# hm2.net
KiCad netlist of a schematic drawn in EAGLE
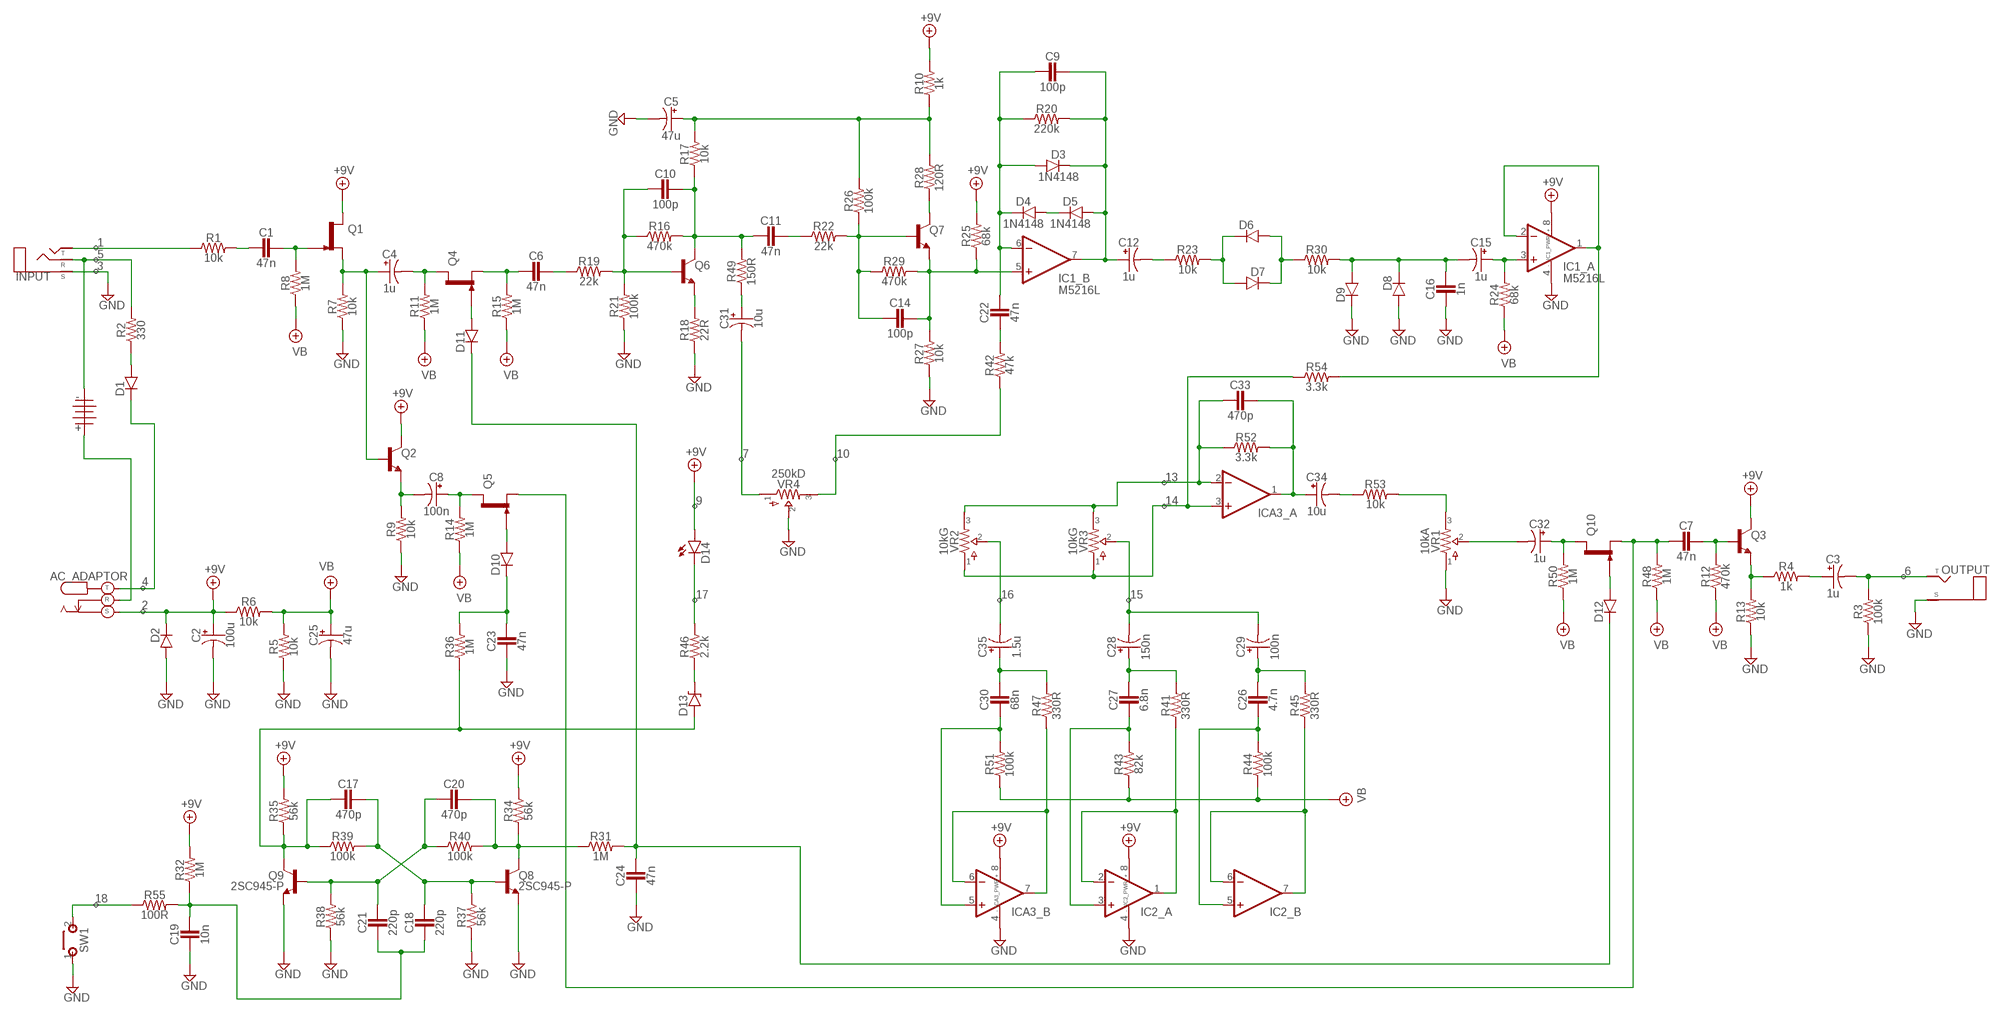
[diagram p0: schematic, sheet 1]

(export (version "E")
  (design (tool "Eeschema 10.0.6"))
  (components
    (comp (ref "1101")
      (value "BATTERY")
      (footprint "eagle-import:TWO_PADS")
      (libsource (lib "eagle-import") (part "BATTERY"))
    )
    (comp (ref "AC_ADAPTOR")
      (value "DC_KOBICONN")
      (footprint "eagle-import:DC_KOBICONN")
      (libsource (lib "eagle-import") (part "DC_KOBICONN"))
    )
    (comp (ref "C1")
      (value "47n")
      (footprint "eagle-import:BOX_SMALL")
      (libsource (lib "eagle-import") (part "CER/FILMBOX.1"))
    )
    (comp (ref "C2")
      (value "100u")
      (footprint "eagle-import:040_020")
      (libsource (lib "eagle-import") (part "0400"))
    )
    (comp (ref "C3")
      (value "1u")
      (footprint "eagle-import:040_020")
      (libsource (lib "eagle-import") (part "0400"))
    )
    (comp (ref "C4")
      (value "1u")
      (footprint "eagle-import:040_020")
      (libsource (lib "eagle-import") (part "0400"))
    )
    (comp (ref "C5")
      (value "47u")
      (footprint "eagle-import:040_020")
      (libsource (lib "eagle-import") (part "0400"))
    )
    (comp (ref "C6")
      (value "47n")
      (footprint "eagle-import:BOX_SMALL")
      (libsource (lib "eagle-import") (part "CER/FILMBOX.1"))
    )
    (comp (ref "C7")
      (value "47n")
      (footprint "eagle-import:BOX_SMALL")
      (libsource (lib "eagle-import") (part "CER/FILMBOX.1"))
    )
    (comp (ref "C8")
      (value "100n")
      (footprint "eagle-import:040_020")
      (libsource (lib "eagle-import") (part "0400"))
    )
    (comp (ref "C9")
      (value "100p")
      (footprint "eagle-import:BOX_SMALL")
      (libsource (lib "eagle-import") (part "CER/FILMBOX.1"))
    )
    (comp (ref "C10")
      (value "100p")
      (footprint "eagle-import:BOX_SMALL")
      (libsource (lib "eagle-import") (part "CER/FILMBOX.1"))
    )
    (comp (ref "C11")
      (value "47n")
      (footprint "eagle-import:BOX_SMALL")
      (libsource (lib "eagle-import") (part "CER/FILMBOX.1"))
    )
    (comp (ref "C12")
      (value "1u")
      (footprint "eagle-import:040_020")
      (libsource (lib "eagle-import") (part "0400"))
    )
    (comp (ref "C14")
      (value "100p")
      (footprint "eagle-import:BOX_SMALL")
      (libsource (lib "eagle-import") (part "CER/FILMBOX.1"))
    )
    (comp (ref "C15")
      (value "1u")
      (footprint "eagle-import:040_020")
      (libsource (lib "eagle-import") (part "0400"))
    )
    (comp (ref "C16")
      (value "1n")
      (footprint "eagle-import:BOX_SMALL")
      (libsource (lib "eagle-import") (part "CER/FILMBOX.1"))
    )
    (comp (ref "C17")
      (value "470p")
      (footprint "eagle-import:BOX_SMALL")
      (libsource (lib "eagle-import") (part "CER/FILMBOX.1"))
    )
    (comp (ref "C18")
      (value "220p")
      (footprint "eagle-import:BOX_SMALL")
      (libsource (lib "eagle-import") (part "CER/FILMBOX.1"))
    )
    (comp (ref "C19")
      (value "10n")
      (footprint "eagle-import:BOX_SMALL")
      (libsource (lib "eagle-import") (part "CER/FILMBOX.1"))
    )
    (comp (ref "C20")
      (value "470p")
      (footprint "eagle-import:BOX_SMALL")
      (libsource (lib "eagle-import") (part "CER/FILMBOX.1"))
    )
    (comp (ref "C21")
      (value "220p")
      (footprint "eagle-import:BOX_SMALL")
      (libsource (lib "eagle-import") (part "CER/FILMBOX.1"))
    )
    (comp (ref "C22")
      (value "47n")
      (footprint "eagle-import:BOX_SMALL")
      (libsource (lib "eagle-import") (part "CER/FILMBOX.1"))
    )
    (comp (ref "C23")
      (value "47n")
      (footprint "eagle-import:BOX_SMALL")
      (libsource (lib "eagle-import") (part "CER/FILMBOX.1"))
    )
    (comp (ref "C24")
      (value "47n")
      (footprint "eagle-import:BOX_SMALL")
      (libsource (lib "eagle-import") (part "CER/FILMBOX.1"))
    )
    (comp (ref "C25")
      (value "47u")
      (footprint "eagle-import:040_020")
      (libsource (lib "eagle-import") (part "0400"))
    )
    (comp (ref "C26")
      (value "4.7n")
      (footprint "eagle-import:BOX_SMALL")
      (libsource (lib "eagle-import") (part "CER/FILMBOX.1"))
    )
    (comp (ref "C27")
      (value "6.8n")
      (footprint "eagle-import:BOX_SMALL")
      (libsource (lib "eagle-import") (part "CER/FILMBOX.1"))
    )
    (comp (ref "C28")
      (value "150n")
      (footprint "eagle-import:040_020")
      (libsource (lib "eagle-import") (part "0400"))
    )
    (comp (ref "C29")
      (value "100n")
      (footprint "eagle-import:040_020")
      (libsource (lib "eagle-import") (part "0400"))
    )
    (comp (ref "C30")
      (value "68n")
      (footprint "eagle-import:BOX_SMALL")
      (libsource (lib "eagle-import") (part "CER/FILMBOX.1"))
    )
    (comp (ref "C31")
      (value "10u")
      (footprint "eagle-import:040_020")
      (libsource (lib "eagle-import") (part "0400"))
    )
    (comp (ref "C32")
      (value "1u")
      (footprint "eagle-import:040_020")
      (libsource (lib "eagle-import") (part "0400"))
    )
    (comp (ref "C33")
      (value "470p")
      (footprint "eagle-import:BOX_SMALL")
      (libsource (lib "eagle-import") (part "CER/FILMBOX.1"))
    )
    (comp (ref "C34")
      (value "10u")
      (footprint "eagle-import:040_020")
      (libsource (lib "eagle-import") (part "0400"))
    )
    (comp (ref "C35")
      (value "1.5u")
      (footprint "eagle-import:040_020")
      (libsource (lib "eagle-import") (part "0400"))
    )
    (comp (ref "D1")
      (value "DO35.2")
      (footprint "eagle-import:DO35-2")
      (libsource (lib "eagle-import") (part "DO35.2"))
    )
    (comp (ref "D2")
      (value "DO35.2")
      (footprint "eagle-import:DO35-2")
      (libsource (lib "eagle-import") (part "DO35.2"))
    )
    (comp (ref "D3")
      (value "1N4148")
      (footprint "eagle-import:DO35-2")
      (libsource (lib "eagle-import") (part "DO35.2"))
    )
    (comp (ref "D4")
      (value "1N4148")
      (footprint "eagle-import:DO35-2")
      (libsource (lib "eagle-import") (part "DO35.2"))
    )
    (comp (ref "D5")
      (value "1N4148")
      (footprint "eagle-import:DO35-2")
      (libsource (lib "eagle-import") (part "DO35.2"))
    )
    (comp (ref "D6")
      (value "DO35.2")
      (footprint "eagle-import:DO35-2")
      (libsource (lib "eagle-import") (part "DO35.2"))
    )
    (comp (ref "D7")
      (value "DO35.2")
      (footprint "eagle-import:DO35-2")
      (libsource (lib "eagle-import") (part "DO35.2"))
    )
    (comp (ref "D8")
      (value "DO35.2")
      (footprint "eagle-import:DO35-2")
      (libsource (lib "eagle-import") (part "DO35.2"))
    )
    (comp (ref "D9")
      (value "DO35.2")
      (footprint "eagle-import:DO35-2")
      (libsource (lib "eagle-import") (part "DO35.2"))
    )
    (comp (ref "D10")
      (value "DO35.2")
      (footprint "eagle-import:DO35-2")
      (libsource (lib "eagle-import") (part "DO35.2"))
    )
    (comp (ref "D11")
      (value "DO35.2")
      (footprint "eagle-import:DO35-2")
      (libsource (lib "eagle-import") (part "DO35.2"))
    )
    (comp (ref "D12")
      (value "DO35.2")
      (footprint "eagle-import:DO35-2")
      (libsource (lib "eagle-import") (part "DO35.2"))
    )
    (comp (ref "D13")
      (value "ZENER.2")
      (footprint "eagle-import:DO41-2")
      (libsource (lib "eagle-import") (part "ZENER.2"))
    )
    (comp (ref "D14")
      (value "LED")
      (footprint "eagle-import:3MM_D")
      (libsource (lib "eagle-import") (part "LED"))
    )
    (comp (ref "IC1")
      (value "M5216L")
      (footprint "eagle-import:DIL0")
      (libsource (lib "eagle-import") (part "DUALTH"))
    )
    (comp (ref "IC2")
      (value "DUALTH")
      (footprint "eagle-import:DIL0")
      (libsource (lib "eagle-import") (part "DUALTH"))
    )
    (comp (ref "ICA3")
      (value "DUALTH")
      (footprint "eagle-import:DIL0")
      (libsource (lib "eagle-import") (part "DUALTH"))
    )
    (comp (ref "INPUT")
      (value "STEREO3PADS")
      (footprint "eagle-import:THREEPADS")
      (libsource (lib "eagle-import") (part "STEREO3PADS"))
    )
    (comp (ref "OUTPUT")
      (value "MONO")
      (footprint "eagle-import:TWO_PADS")
      (libsource (lib "eagle-import") (part "MONO"))
    )
    (comp (ref "Q1")
      (value "2N5457")
      (footprint "eagle-import:TO92-")
      (libsource (lib "eagle-import") (part "2N5457"))
    )
    (comp (ref "Q2")
      (value "2SC828A")
      (footprint "eagle-import:TO92-")
      (libsource (lib "eagle-import") (part "2SC828A"))
    )
    (comp (ref "Q3")
      (value "2SC828A")
      (footprint "eagle-import:TO92-")
      (libsource (lib "eagle-import") (part "2SC828A"))
    )
    (comp (ref "Q4")
      (value "2N5457")
      (footprint "eagle-import:TO92-")
      (libsource (lib "eagle-import") (part "2N5457"))
    )
    (comp (ref "Q5")
      (value "2N5457")
      (footprint "eagle-import:TO92-")
      (libsource (lib "eagle-import") (part "2N5457"))
    )
    (comp (ref "Q6")
      (value "2SC828A")
      (footprint "eagle-import:TO92-")
      (libsource (lib "eagle-import") (part "2SC828A"))
    )
    (comp (ref "Q7")
      (value "2SC828A")
      (footprint "eagle-import:TO92-")
      (libsource (lib "eagle-import") (part "2SC828A"))
    )
    (comp (ref "Q8")
      (value "2SC945-P")
      (footprint "eagle-import:TO92-")
      (libsource (lib "eagle-import") (part "2SC828A"))
    )
    (comp (ref "Q9")
      (value "2SC945-P")
      (footprint "eagle-import:TO92-")
      (libsource (lib "eagle-import") (part "2SC828A"))
    )
    (comp (ref "Q10")
      (value "2N5457")
      (footprint "eagle-import:TO92-")
      (libsource (lib "eagle-import") (part "2N5457"))
    )
    (comp (ref "R1")
      (value "10k")
      (footprint "eagle-import:R0207_3")
      (libsource (lib "eagle-import") (part "R_.3B"))
    )
    (comp (ref "R2")
      (value "330")
      (footprint "eagle-import:R0207_3")
      (libsource (lib "eagle-import") (part "R_.3B"))
    )
    (comp (ref "R3")
      (value "100k")
      (footprint "eagle-import:R0207_3")
      (libsource (lib "eagle-import") (part "R_.3B"))
    )
    (comp (ref "R4")
      (value "1k")
      (footprint "eagle-import:R0207_3")
      (libsource (lib "eagle-import") (part "R_.3B"))
    )
    (comp (ref "R5")
      (value "10k")
      (footprint "eagle-import:R0207_3")
      (libsource (lib "eagle-import") (part "R_.3B"))
    )
    (comp (ref "R6")
      (value "10k")
      (footprint "eagle-import:R0207_3")
      (libsource (lib "eagle-import") (part "R_.3B"))
    )
    (comp (ref "R7")
      (value "10k")
      (footprint "eagle-import:R0207_3")
      (libsource (lib "eagle-import") (part "R_.3B"))
    )
    (comp (ref "R8")
      (value "1M")
      (footprint "eagle-import:R0207_3")
      (libsource (lib "eagle-import") (part "R_.3B"))
    )
    (comp (ref "R9")
      (value "10k")
      (footprint "eagle-import:R0207_3")
      (libsource (lib "eagle-import") (part "R_.3B"))
    )
    (comp (ref "R10")
      (value "1k")
      (footprint "eagle-import:R0207_3")
      (libsource (lib "eagle-import") (part "R_.3B"))
    )
    (comp (ref "R11")
      (value "1M")
      (footprint "eagle-import:R0207_3")
      (libsource (lib "eagle-import") (part "R_.3B"))
    )
    (comp (ref "R12")
      (value "470k")
      (footprint "eagle-import:R0207_3")
      (libsource (lib "eagle-import") (part "R_.3B"))
    )
    (comp (ref "R13")
      (value "10k")
      (footprint "eagle-import:R0207_3")
      (libsource (lib "eagle-import") (part "R_.3B"))
    )
    (comp (ref "R14")
      (value "1M")
      (footprint "eagle-import:R0207_3")
      (libsource (lib "eagle-import") (part "R_.3B"))
    )
    (comp (ref "R15")
      (value "1M")
      (footprint "eagle-import:R0207_3")
      (libsource (lib "eagle-import") (part "R_.3B"))
    )
    (comp (ref "R16")
      (value "470k")
      (footprint "eagle-import:R0207_3")
      (libsource (lib "eagle-import") (part "R_.3B"))
    )
    (comp (ref "R17")
      (value "10k")
      (footprint "eagle-import:R0207_3")
      (libsource (lib "eagle-import") (part "R_.3B"))
    )
    (comp (ref "R18")
      (value "22R")
      (footprint "eagle-import:R0207_3")
      (libsource (lib "eagle-import") (part "R_.3B"))
    )
    (comp (ref "R19")
      (value "22k")
      (footprint "eagle-import:R0207_3")
      (libsource (lib "eagle-import") (part "R_.3B"))
    )
    (comp (ref "R20")
      (value "220k")
      (footprint "eagle-import:R0207_3")
      (libsource (lib "eagle-import") (part "R_.3B"))
    )
    (comp (ref "R21")
      (value "100k")
      (footprint "eagle-import:R0207_3")
      (libsource (lib "eagle-import") (part "R_.3B"))
    )
    (comp (ref "R22")
      (value "22k")
      (footprint "eagle-import:R0207_3")
      (libsource (lib "eagle-import") (part "R_.3B"))
    )
    (comp (ref "R23")
      (value "10k")
      (footprint "eagle-import:R0207_3")
      (libsource (lib "eagle-import") (part "R_.3B"))
    )
    (comp (ref "R24")
      (value "68k")
      (footprint "eagle-import:R0207_3")
      (libsource (lib "eagle-import") (part "R_.3B"))
    )
    (comp (ref "R25")
      (value "68k")
      (footprint "eagle-import:R0207_3")
      (libsource (lib "eagle-import") (part "R_.3B"))
    )
    (comp (ref "R26")
      (value "100k")
      (footprint "eagle-import:R0207_3")
      (libsource (lib "eagle-import") (part "R_.3B"))
    )
    (comp (ref "R27")
      (value "10k")
      (footprint "eagle-import:R0207_3")
      (libsource (lib "eagle-import") (part "R_.3B"))
    )
    (comp (ref "R28")
      (value "120R")
      (footprint "eagle-import:R0207_3")
      (libsource (lib "eagle-import") (part "R_.3B"))
    )
    (comp (ref "R29")
      (value "470k")
      (footprint "eagle-import:R0207_3")
      (libsource (lib "eagle-import") (part "R_.3B"))
    )
    (comp (ref "R30")
      (value "10k")
      (footprint "eagle-import:R0207_3")
      (libsource (lib "eagle-import") (part "R_.3B"))
    )
    (comp (ref "R31")
      (value "1M")
      (footprint "eagle-import:R0207_3")
      (libsource (lib "eagle-import") (part "R_.3B"))
    )
    (comp (ref "R32")
      (value "1M")
      (footprint "eagle-import:R0207_3")
      (libsource (lib "eagle-import") (part "R_.3B"))
    )
    (comp (ref "R34")
      (value "56k")
      (footprint "eagle-import:R0207_3")
      (libsource (lib "eagle-import") (part "R_.3B"))
    )
    (comp (ref "R35")
      (value "56k")
      (footprint "eagle-import:R0207_3")
      (libsource (lib "eagle-import") (part "R_.3B"))
    )
    (comp (ref "R36")
      (value "1M")
      (footprint "eagle-import:R0207_3")
      (libsource (lib "eagle-import") (part "R_.3B"))
    )
    (comp (ref "R37")
      (value "56k")
      (footprint "eagle-import:R0207_3")
      (libsource (lib "eagle-import") (part "R_.3B"))
    )
    (comp (ref "R38")
      (value "56k")
      (footprint "eagle-import:R0207_3")
      (libsource (lib "eagle-import") (part "R_.3B"))
    )
    (comp (ref "R39")
      (value "100k")
      (footprint "eagle-import:R0207_3")
      (libsource (lib "eagle-import") (part "R_.3B"))
    )
    (comp (ref "R40")
      (value "100k")
      (footprint "eagle-import:R0207_3")
      (libsource (lib "eagle-import") (part "R_.3B"))
    )
    (comp (ref "R41")
      (value "330R")
      (footprint "eagle-import:R0207_3")
      (libsource (lib "eagle-import") (part "R_.3B"))
    )
    (comp (ref "R42")
      (value "47k")
      (footprint "eagle-import:R0207_3")
      (libsource (lib "eagle-import") (part "R_.3B"))
    )
    (comp (ref "R43")
      (value "82k")
      (footprint "eagle-import:R0207_3")
      (libsource (lib "eagle-import") (part "R_.3B"))
    )
    (comp (ref "R44")
      (value "100k")
      (footprint "eagle-import:R0207_3")
      (libsource (lib "eagle-import") (part "R_.3B"))
    )
    (comp (ref "R45")
      (value "330R")
      (footprint "eagle-import:R0207_3")
      (libsource (lib "eagle-import") (part "R_.3B"))
    )
    (comp (ref "R46")
      (value "2.2k")
      (footprint "eagle-import:R0207_3")
      (libsource (lib "eagle-import") (part "R_.3B"))
    )
    (comp (ref "R47")
      (value "330R")
      (footprint "eagle-import:R0207_3")
      (libsource (lib "eagle-import") (part "R_.3B"))
    )
    (comp (ref "R48")
      (value "1M")
      (footprint "eagle-import:R0207_3")
      (libsource (lib "eagle-import") (part "R_.3B"))
    )
    (comp (ref "R49")
      (value "150R")
      (footprint "eagle-import:R0207_3")
      (libsource (lib "eagle-import") (part "R_.3B"))
    )
    (comp (ref "R50")
      (value "1M")
      (footprint "eagle-import:R0207_3")
      (libsource (lib "eagle-import") (part "R_.3B"))
    )
    (comp (ref "R51")
      (value "100k")
      (footprint "eagle-import:R0207_3")
      (libsource (lib "eagle-import") (part "R_.3B"))
    )
    (comp (ref "R52")
      (value "3.3k")
      (footprint "eagle-import:R0207_3")
      (libsource (lib "eagle-import") (part "R_.3B"))
    )
    (comp (ref "R53")
      (value "10k")
      (footprint "eagle-import:R0207_3")
      (libsource (lib "eagle-import") (part "R_.3B"))
    )
    (comp (ref "R54")
      (value "3.3k")
      (footprint "eagle-import:R0207_3")
      (libsource (lib "eagle-import") (part "R_.3B"))
    )
    (comp (ref "R55")
      (value "100R")
      (footprint "eagle-import:R0207_3")
      (libsource (lib "eagle-import") (part "R_.3B"))
    )
    (comp (ref "SW1")
      (value "MOMENTARY")
      (footprint "eagle-import:SPST")
      (libsource (lib "eagle-import") (part "MOMENTARY"))
    )
    (comp (ref "VR1")
      (value "10kA")
      (footprint "eagle-import:16MM")
      (libsource (lib "eagle-import") (part "POTS16MM"))
    )
    (comp (ref "VR2")
      (value "10kG")
      (footprint "eagle-import:16MM")
      (libsource (lib "eagle-import") (part "POTS16MM"))
    )
    (comp (ref "VR3")
      (value "10kG")
      (footprint "eagle-import:16MM")
      (libsource (lib "eagle-import") (part "POTS16MM"))
    )
    (comp (ref "VR4")
      (value "250kD")
      (footprint "eagle-import:16MM")
      (libsource (lib "eagle-import") (part "POTS16MM"))
    )
  )
  (nets
    (net (code "1") (name "+9V") (class "Default")
      (node (ref "AC_ADAPTOR") (pin "S") (pinfunction "S_S") (pintype "bidirectional"))
      (node (ref "C2") (pin "+") (pinfunction "+_+") (pintype "passive"))
      (node (ref "D14") (pin "ANODE") (pinfunction "A_ANODE") (pintype "passive"))
      (node (ref "D2") (pin "C") (pinfunction "C_C") (pintype "passive"))
      (node (ref "IC1") (pin "8") (pinfunction "V+_8") (pintype "power_in"))
      (node (ref "IC2") (pin "8") (pinfunction "V+_8") (pintype "power_in"))
      (node (ref "ICA3") (pin "8") (pinfunction "V+_8") (pintype "power_in"))
      (node (ref "Q1") (pin "3") (pinfunction "D_3") (pintype "passive"))
      (node (ref "Q2") (pin "2") (pinfunction "C_2") (pintype "passive"))
      (node (ref "Q3") (pin "2") (pinfunction "C_2") (pintype "passive"))
      (node (ref "R10") (pin "2") (pinfunction "2_2") (pintype "passive"))
      (node (ref "R25") (pin "2") (pinfunction "2_2") (pintype "passive"))
      (node (ref "R32") (pin "2") (pinfunction "2_2") (pintype "passive"))
      (node (ref "R34") (pin "2") (pinfunction "2_2") (pintype "passive"))
      (node (ref "R35") (pin "2") (pinfunction "2_2") (pintype "passive"))
      (node (ref "R6") (pin "1") (pinfunction "1_1") (pintype "passive"))
    )
    (net (code "2") (name "GND") (class "Default")
      (node (ref "C16") (pin "2") (pinfunction "2_2") (pintype "passive"))
      (node (ref "C19") (pin "2") (pinfunction "2_2") (pintype "passive"))
      (node (ref "C2") (pin "-") (pinfunction "-_-") (pintype "passive"))
      (node (ref "C23") (pin "2") (pinfunction "2_2") (pintype "passive"))
      (node (ref "C24") (pin "2") (pinfunction "2_2") (pintype "passive"))
      (node (ref "C25") (pin "-") (pinfunction "-_-") (pintype "passive"))
      (node (ref "C5") (pin "-") (pinfunction "-_-") (pintype "passive"))
      (node (ref "D2") (pin "A") (pinfunction "A_A") (pintype "passive"))
      (node (ref "D8") (pin "A") (pinfunction "A_A") (pintype "passive"))
      (node (ref "D9") (pin "C") (pinfunction "C_C") (pintype "passive"))
      (node (ref "IC1") (pin "4") (pinfunction "V-_4") (pintype "power_in"))
      (node (ref "IC2") (pin "4") (pinfunction "V-_4") (pintype "power_in"))
      (node (ref "ICA3") (pin "4") (pinfunction "V-_4") (pintype "power_in"))
      (node (ref "INPUT") (pin "SLEEVE") (pinfunction "S_SLEEVE") (pintype "passive"))
      (node (ref "OUTPUT") (pin "S") (pinfunction "SLEEVE_S") (pintype "passive"))
      (node (ref "Q8") (pin "3") (pinfunction "E_3") (pintype "passive"))
      (node (ref "Q9") (pin "3") (pinfunction "E_3") (pintype "passive"))
      (node (ref "R13") (pin "1") (pinfunction "1_1") (pintype "passive"))
      (node (ref "R18") (pin "1") (pinfunction "1_1") (pintype "passive"))
      (node (ref "R21") (pin "1") (pinfunction "1_1") (pintype "passive"))
      (node (ref "R27") (pin "1") (pinfunction "1_1") (pintype "passive"))
      (node (ref "R3") (pin "1") (pinfunction "1_1") (pintype "passive"))
      (node (ref "R37") (pin "1") (pinfunction "1_1") (pintype "passive"))
      (node (ref "R38") (pin "1") (pinfunction "1_1") (pintype "passive"))
      (node (ref "R5") (pin "1") (pinfunction "1_1") (pintype "passive"))
      (node (ref "R7") (pin "1") (pinfunction "1_1") (pintype "passive"))
      (node (ref "R9") (pin "1") (pinfunction "1_1") (pintype "passive"))
      (node (ref "SW1") (pin "1") (pinfunction "P_1") (pintype "passive"))
      (node (ref "VR1") (pin "1") (pinfunction "1_1") (pintype "passive"))
      (node (ref "VR4") (pin "2") (pinfunction "2_2") (pintype "passive"))
    )
    (net (code "3") (name "Net-(1101-P$1)") (class "Default")
      (node (ref "1101") (pin "T") (pinfunction "P$1_T") (pintype "bidirectional"))
      (node (ref "AC_ADAPTOR") (pin "R") (pinfunction "R_R") (pintype "bidirectional"))
    )
    (net (code "4") (name "Net-(1101-P$2)") (class "Default")
      (node (ref "1101") (pin "S") (pinfunction "P$2_S") (pintype "bidirectional"))
      (node (ref "INPUT") (pin "RING") (pinfunction "R_RING") (pintype "passive"))
      (node (ref "R2") (pin "2") (pinfunction "2_2") (pintype "passive"))
    )
    (net (code "5") (name "Net-(AC_ADAPTOR-PadT)") (class "Default")
      (node (ref "AC_ADAPTOR") (pin "T") (pinfunction "T_T") (pintype "bidirectional"))
      (node (ref "D1") (pin "C") (pinfunction "C_C") (pintype "passive"))
    )
    (net (code "6") (name "Net-(C1-Pad2)") (class "Default")
      (node (ref "C1") (pin "2") (pinfunction "2_2") (pintype "passive"))
      (node (ref "R1") (pin "2") (pinfunction "2_2") (pintype "passive"))
    )
    (net (code "7") (name "Net-(C3-Pad+)") (class "Default")
      (node (ref "C3") (pin "+") (pinfunction "+_+") (pintype "passive"))
      (node (ref "R4") (pin "2") (pinfunction "2_2") (pintype "passive"))
    )
    (net (code "8") (name "Net-(C5-Pad+)") (class "Default")
      (node (ref "C5") (pin "+") (pinfunction "+_+") (pintype "passive"))
      (node (ref "R10") (pin "1") (pinfunction "1_1") (pintype "passive"))
      (node (ref "R17") (pin "2") (pinfunction "2_2") (pintype "passive"))
      (node (ref "R26") (pin "2") (pinfunction "2_2") (pintype "passive"))
      (node (ref "R28") (pin "2") (pinfunction "2_2") (pintype "passive"))
    )
    (net (code "9") (name "Net-(C6-Pad1)") (class "Default")
      (node (ref "C6") (pin "1") (pinfunction "1_1") (pintype "passive"))
      (node (ref "R19") (pin "1") (pinfunction "1_1") (pintype "passive"))
    )
    (net (code "10") (name "Net-(C11-Pad1)") (class "Default")
      (node (ref "C11") (pin "1") (pinfunction "1_1") (pintype "passive"))
      (node (ref "R22") (pin "1") (pinfunction "1_1") (pintype "passive"))
    )
    (net (code "11") (name "Net-(C12-Pad-)") (class "Default")
      (node (ref "C12") (pin "-") (pinfunction "-_-") (pintype "passive"))
      (node (ref "R23") (pin "1") (pinfunction "1_1") (pintype "passive"))
    )
    (net (code "12") (name "Net-(C15-Pad-)") (class "Default")
      (node (ref "C15") (pin "-") (pinfunction "-_-") (pintype "passive"))
      (node (ref "C16") (pin "1") (pinfunction "1_1") (pintype "passive"))
      (node (ref "D8") (pin "C") (pinfunction "C_C") (pintype "passive"))
      (node (ref "D9") (pin "A") (pinfunction "A_A") (pintype "passive"))
      (node (ref "R30") (pin "2") (pinfunction "2_2") (pintype "passive"))
    )
    (net (code "13") (name "Net-(C18-Pad2)") (class "Default")
      (node (ref "C18") (pin "2") (pinfunction "2_2") (pintype "passive"))
      (node (ref "C19") (pin "1") (pinfunction "1_1") (pintype "passive"))
      (node (ref "C21") (pin "2") (pinfunction "2_2") (pintype "passive"))
      (node (ref "R32") (pin "1") (pinfunction "1_1") (pintype "passive"))
      (node (ref "R55") (pin "2") (pinfunction "2_2") (pintype "passive"))
    )
    (net (code "14") (name "Net-(C22-Pad2)") (class "Default")
      (node (ref "C22") (pin "2") (pinfunction "2_2") (pintype "passive"))
      (node (ref "R42") (pin "2") (pinfunction "2_2") (pintype "passive"))
    )
    (net (code "15") (name "Net-(C23-Pad1)") (class "Default")
      (node (ref "C23") (pin "1") (pinfunction "1_1") (pintype "passive"))
      (node (ref "D10") (pin "C") (pinfunction "C_C") (pintype "passive"))
      (node (ref "R36") (pin "2") (pinfunction "2_2") (pintype "passive"))
    )
    (net (code "16") (name "Net-(C24-Pad1)") (class "Default")
      (node (ref "C24") (pin "1") (pinfunction "1_1") (pintype "passive"))
      (node (ref "D11") (pin "C") (pinfunction "C_C") (pintype "passive"))
      (node (ref "D12") (pin "C") (pinfunction "C_C") (pintype "passive"))
      (node (ref "R31") (pin "2") (pinfunction "2_2") (pintype "passive"))
    )
    (net (code "17") (name "Net-(C26-Pad1)") (class "Default")
      (node (ref "C26") (pin "1") (pinfunction "1_1") (pintype "passive"))
      (node (ref "C29") (pin "+") (pinfunction "+_+") (pintype "passive"))
      (node (ref "R45") (pin "2") (pinfunction "2_2") (pintype "passive"))
    )
    (net (code "18") (name "Net-(C27-Pad1)") (class "Default")
      (node (ref "C27") (pin "1") (pinfunction "1_1") (pintype "passive"))
      (node (ref "C28") (pin "+") (pinfunction "+_+") (pintype "passive"))
      (node (ref "R41") (pin "2") (pinfunction "2_2") (pintype "passive"))
    )
    (net (code "19") (name "Net-(C28-Pad-)") (class "Default")
      (node (ref "C28") (pin "-") (pinfunction "-_-") (pintype "passive"))
      (node (ref "C29") (pin "-") (pinfunction "-_-") (pintype "passive"))
      (node (ref "VR3") (pin "2") (pinfunction "2_2") (pintype "passive"))
    )
    (net (code "20") (name "Net-(C30-Pad1)") (class "Default")
      (node (ref "C30") (pin "1") (pinfunction "1_1") (pintype "passive"))
      (node (ref "C35") (pin "+") (pinfunction "+_+") (pintype "passive"))
      (node (ref "R47") (pin "2") (pinfunction "2_2") (pintype "passive"))
    )
    (net (code "21") (name "Net-(C31-Pad+)") (class "Default")
      (node (ref "C31") (pin "+") (pinfunction "+_+") (pintype "passive"))
      (node (ref "R49") (pin "1") (pinfunction "1_1") (pintype "passive"))
    )
    (net (code "22") (name "Net-(C31-Pad-)") (class "Default")
      (node (ref "C31") (pin "-") (pinfunction "-_-") (pintype "passive"))
      (node (ref "VR4") (pin "1") (pinfunction "1_1") (pintype "passive"))
    )
    (net (code "23") (name "Net-(C32-Pad-)") (class "Default")
      (node (ref "C32") (pin "-") (pinfunction "-_-") (pintype "passive"))
      (node (ref "VR1") (pin "2") (pinfunction "2_2") (pintype "passive"))
    )
    (net (code "24") (name "Net-(C34-Pad-)") (class "Default")
      (node (ref "C34") (pin "-") (pinfunction "-_-") (pintype "passive"))
      (node (ref "R53") (pin "1") (pinfunction "1_1") (pintype "passive"))
    )
    (net (code "25") (name "Net-(C35-Pad-)") (class "Default")
      (node (ref "C35") (pin "-") (pinfunction "-_-") (pintype "passive"))
      (node (ref "VR2") (pin "2") (pinfunction "2_2") (pintype "passive"))
    )
    (net (code "26") (name "Net-(D1-PadA)") (class "Default")
      (node (ref "D1") (pin "A") (pinfunction "A_A") (pintype "passive"))
      (node (ref "R2") (pin "1") (pinfunction "1_1") (pintype "passive"))
    )
    (net (code "27") (name "Net-(D4-PadA)") (class "Default")
      (node (ref "D4") (pin "A") (pinfunction "A_A") (pintype "passive"))
      (node (ref "D5") (pin "C") (pinfunction "C_C") (pintype "passive"))
    )
    (net (code "28") (name "Net-(D6-PadA)") (class "Default")
      (node (ref "D6") (pin "A") (pinfunction "A_A") (pintype "passive"))
      (node (ref "D7") (pin "C") (pinfunction "C_C") (pintype "passive"))
      (node (ref "R30") (pin "1") (pinfunction "1_1") (pintype "passive"))
    )
    (net (code "29") (name "Net-(D6-PadC)") (class "Default")
      (node (ref "D6") (pin "C") (pinfunction "C_C") (pintype "passive"))
      (node (ref "D7") (pin "A") (pinfunction "A_A") (pintype "passive"))
      (node (ref "R23") (pin "2") (pinfunction "2_2") (pintype "passive"))
    )
    (net (code "30") (name "Net-(D13-PadC)") (class "Default")
      (node (ref "D13") (pin "C") (pinfunction "C_C") (pintype "passive"))
      (node (ref "R46") (pin "1") (pinfunction "1_1") (pintype "passive"))
    )
    (net (code "31") (name "Net-(D14-C)") (class "Default")
      (node (ref "D14") (pin "P$1") (pinfunction "C_P$1") (pintype "passive"))
      (node (ref "R46") (pin "2") (pinfunction "2_2") (pintype "passive"))
    )
    (net (code "32") (name "Net-(IC1A-+IN)") (class "Default")
      (node (ref "C15") (pin "+") (pinfunction "+_+") (pintype "passive"))
      (node (ref "IC1") (pin "3") (pinfunction "+IN_3") (pintype "input"))
      (node (ref "R24") (pin "2") (pinfunction "2_2") (pintype "passive"))
    )
    (net (code "33") (name "Net-(IC1A--IN)") (class "Default")
      (node (ref "IC1") (pin "1") (pinfunction "OUT_1") (pintype "output"))
      (node (ref "IC1") (pin "2") (pinfunction "-IN_2") (pintype "input"))
      (node (ref "R54") (pin "2") (pinfunction "2_2") (pintype "passive"))
    )
    (net (code "34") (name "Net-(IC1B-+IN)") (class "Default")
      (node (ref "C14") (pin "1") (pinfunction "1_1") (pintype "passive"))
      (node (ref "IC1") (pin "5") (pinfunction "+IN_5") (pintype "input"))
      (node (ref "Q7") (pin "3") (pinfunction "E_3") (pintype "passive"))
      (node (ref "R25") (pin "1") (pinfunction "1_1") (pintype "passive"))
      (node (ref "R27") (pin "2") (pinfunction "2_2") (pintype "passive"))
      (node (ref "R29") (pin "2") (pinfunction "2_2") (pintype "passive"))
    )
    (net (code "35") (name "Net-(IC1B--IN)") (class "Default")
      (node (ref "C22") (pin "1") (pinfunction "1_1") (pintype "passive"))
      (node (ref "C9") (pin "2") (pinfunction "2_2") (pintype "passive"))
      (node (ref "D3") (pin "A") (pinfunction "A_A") (pintype "passive"))
      (node (ref "D4") (pin "C") (pinfunction "C_C") (pintype "passive"))
      (node (ref "IC1") (pin "6") (pinfunction "-IN_6") (pintype "input"))
      (node (ref "R20") (pin "1") (pinfunction "1_1") (pintype "passive"))
    )
    (net (code "36") (name "Net-(IC1B-OUT)") (class "Default")
      (node (ref "C12") (pin "+") (pinfunction "+_+") (pintype "passive"))
      (node (ref "C9") (pin "1") (pinfunction "1_1") (pintype "passive"))
      (node (ref "D3") (pin "C") (pinfunction "C_C") (pintype "passive"))
      (node (ref "D5") (pin "A") (pinfunction "A_A") (pintype "passive"))
      (node (ref "IC1") (pin "7") (pinfunction "OUT_7") (pintype "output"))
      (node (ref "R20") (pin "2") (pinfunction "2_2") (pintype "passive"))
    )
    (net (code "37") (name "Net-(IC2A-+IN)") (class "Default")
      (node (ref "C27") (pin "2") (pinfunction "2_2") (pintype "passive"))
      (node (ref "IC2") (pin "3") (pinfunction "+IN_3") (pintype "input"))
      (node (ref "R43") (pin "2") (pinfunction "2_2") (pintype "passive"))
    )
    (net (code "38") (name "Net-(IC2A--IN)") (class "Default")
      (node (ref "IC2") (pin "1") (pinfunction "OUT_1") (pintype "output"))
      (node (ref "IC2") (pin "2") (pinfunction "-IN_2") (pintype "input"))
      (node (ref "R41") (pin "1") (pinfunction "1_1") (pintype "passive"))
    )
    (net (code "39") (name "Net-(IC2B-+IN)") (class "Default")
      (node (ref "C26") (pin "2") (pinfunction "2_2") (pintype "passive"))
      (node (ref "IC2") (pin "5") (pinfunction "+IN_5") (pintype "input"))
      (node (ref "R44") (pin "2") (pinfunction "2_2") (pintype "passive"))
    )
    (net (code "40") (name "Net-(IC2B--IN)") (class "Default")
      (node (ref "IC2") (pin "6") (pinfunction "-IN_6") (pintype "input"))
      (node (ref "IC2") (pin "7") (pinfunction "OUT_7") (pintype "output"))
      (node (ref "R45") (pin "1") (pinfunction "1_1") (pintype "passive"))
    )
    (net (code "41") (name "Net-(ICA3A-+IN)") (class "Default")
      (node (ref "ICA3") (pin "3") (pinfunction "+IN_3") (pintype "input"))
      (node (ref "R54") (pin "1") (pinfunction "1_1") (pintype "passive"))
      (node (ref "VR2") (pin "1") (pinfunction "1_1") (pintype "passive"))
      (node (ref "VR3") (pin "1") (pinfunction "1_1") (pintype "passive"))
    )
    (net (code "42") (name "Net-(ICA3A--IN)") (class "Default")
      (node (ref "C33") (pin "2") (pinfunction "2_2") (pintype "passive"))
      (node (ref "ICA3") (pin "2") (pinfunction "-IN_2") (pintype "input"))
      (node (ref "R52") (pin "1") (pinfunction "1_1") (pintype "passive"))
      (node (ref "VR2") (pin "3") (pinfunction "3_3") (pintype "passive"))
      (node (ref "VR3") (pin "3") (pinfunction "3_3") (pintype "passive"))
    )
    (net (code "43") (name "Net-(ICA3A-OUT)") (class "Default")
      (node (ref "C33") (pin "1") (pinfunction "1_1") (pintype "passive"))
      (node (ref "C34") (pin "+") (pinfunction "+_+") (pintype "passive"))
      (node (ref "ICA3") (pin "1") (pinfunction "OUT_1") (pintype "output"))
      (node (ref "R52") (pin "2") (pinfunction "2_2") (pintype "passive"))
    )
    (net (code "44") (name "Net-(ICA3B-+IN)") (class "Default")
      (node (ref "C30") (pin "2") (pinfunction "2_2") (pintype "passive"))
      (node (ref "ICA3") (pin "5") (pinfunction "+IN_5") (pintype "input"))
      (node (ref "R51") (pin "2") (pinfunction "2_2") (pintype "passive"))
    )
    (net (code "45") (name "Net-(ICA3B--IN)") (class "Default")
      (node (ref "ICA3") (pin "6") (pinfunction "-IN_6") (pintype "input"))
      (node (ref "ICA3") (pin "7") (pinfunction "OUT_7") (pintype "output"))
      (node (ref "R47") (pin "1") (pinfunction "1_1") (pintype "passive"))
    )
    (net (code "46") (name "Net-(INPUT-T)") (class "Default")
      (node (ref "INPUT") (pin "TIP") (pinfunction "T_TIP") (pintype "passive"))
      (node (ref "R1") (pin "1") (pinfunction "1_1") (pintype "passive"))
    )
    (net (code "47") (name "Net-(OUTPUT-TIP)") (class "Default")
      (node (ref "C3") (pin "-") (pinfunction "-_-") (pintype "passive"))
      (node (ref "OUTPUT") (pin "T") (pinfunction "TIP_T") (pintype "passive"))
      (node (ref "R3") (pin "2") (pinfunction "2_2") (pintype "passive"))
    )
    (net (code "48") (name "Net-(Q1-G)") (class "Default")
      (node (ref "C1") (pin "1") (pinfunction "1_1") (pintype "passive"))
      (node (ref "Q1") (pin "1") (pinfunction "G_1") (pintype "passive"))
      (node (ref "R8") (pin "2") (pinfunction "2_2") (pintype "passive"))
    )
    (net (code "49") (name "Net-(Q1-S)") (class "Default")
      (node (ref "C4") (pin "+") (pinfunction "+_+") (pintype "passive"))
      (node (ref "Q1") (pin "2") (pinfunction "S_2") (pintype "passive"))
      (node (ref "Q2") (pin "1") (pinfunction "B_1") (pintype "passive"))
      (node (ref "R7") (pin "2") (pinfunction "2_2") (pintype "passive"))
    )
    (net (code "50") (name "Net-(Q2-E)") (class "Default")
      (node (ref "C8") (pin "-") (pinfunction "-_-") (pintype "passive"))
      (node (ref "Q2") (pin "3") (pinfunction "E_3") (pintype "passive"))
      (node (ref "R9") (pin "2") (pinfunction "2_2") (pintype "passive"))
    )
    (net (code "51") (name "Net-(Q3-B)") (class "Default")
      (node (ref "C7") (pin "1") (pinfunction "1_1") (pintype "passive"))
      (node (ref "Q3") (pin "1") (pinfunction "B_1") (pintype "passive"))
      (node (ref "R12") (pin "2") (pinfunction "2_2") (pintype "passive"))
    )
    (net (code "52") (name "Net-(Q3-E)") (class "Default")
      (node (ref "Q3") (pin "3") (pinfunction "E_3") (pintype "passive"))
      (node (ref "R13") (pin "2") (pinfunction "2_2") (pintype "passive"))
      (node (ref "R4") (pin "1") (pinfunction "1_1") (pintype "passive"))
    )
    (net (code "53") (name "Net-(Q4-D)") (class "Default")
      (node (ref "C4") (pin "-") (pinfunction "-_-") (pintype "passive"))
      (node (ref "Q4") (pin "3") (pinfunction "D_3") (pintype "passive"))
      (node (ref "R11") (pin "2") (pinfunction "2_2") (pintype "passive"))
    )
    (net (code "54") (name "Net-(Q4-G)") (class "Default")
      (node (ref "D11") (pin "A") (pinfunction "A_A") (pintype "passive"))
      (node (ref "Q4") (pin "1") (pinfunction "G_1") (pintype "passive"))
    )
    (net (code "55") (name "Net-(Q4-S)") (class "Default")
      (node (ref "C6") (pin "2") (pinfunction "2_2") (pintype "passive"))
      (node (ref "Q4") (pin "2") (pinfunction "S_2") (pintype "passive"))
      (node (ref "R15") (pin "2") (pinfunction "2_2") (pintype "passive"))
    )
    (net (code "56") (name "Net-(Q5-D)") (class "Default")
      (node (ref "C8") (pin "+") (pinfunction "+_+") (pintype "passive"))
      (node (ref "Q5") (pin "3") (pinfunction "D_3") (pintype "passive"))
      (node (ref "R14") (pin "2") (pinfunction "2_2") (pintype "passive"))
    )
    (net (code "57") (name "Net-(Q5-G)") (class "Default")
      (node (ref "D10") (pin "A") (pinfunction "A_A") (pintype "passive"))
      (node (ref "Q5") (pin "1") (pinfunction "G_1") (pintype "passive"))
    )
    (net (code "58") (name "Net-(Q6-B)") (class "Default")
      (node (ref "C10") (pin "2") (pinfunction "2_2") (pintype "passive"))
      (node (ref "Q6") (pin "1") (pinfunction "B_1") (pintype "passive"))
      (node (ref "R16") (pin "1") (pinfunction "1_1") (pintype "passive"))
      (node (ref "R19") (pin "2") (pinfunction "2_2") (pintype "passive"))
      (node (ref "R21") (pin "2") (pinfunction "2_2") (pintype "passive"))
    )
    (net (code "59") (name "Net-(Q6-C)") (class "Default")
      (node (ref "C10") (pin "1") (pinfunction "1_1") (pintype "passive"))
      (node (ref "C11") (pin "2") (pinfunction "2_2") (pintype "passive"))
      (node (ref "Q6") (pin "2") (pinfunction "C_2") (pintype "passive"))
      (node (ref "R16") (pin "2") (pinfunction "2_2") (pintype "passive"))
      (node (ref "R17") (pin "1") (pinfunction "1_1") (pintype "passive"))
      (node (ref "R49") (pin "2") (pinfunction "2_2") (pintype "passive"))
    )
    (net (code "60") (name "Net-(Q6-E)") (class "Default")
      (node (ref "Q6") (pin "3") (pinfunction "E_3") (pintype "passive"))
      (node (ref "R18") (pin "2") (pinfunction "2_2") (pintype "passive"))
    )
    (net (code "61") (name "Net-(Q7-B)") (class "Default")
      (node (ref "C14") (pin "2") (pinfunction "2_2") (pintype "passive"))
      (node (ref "Q7") (pin "1") (pinfunction "B_1") (pintype "passive"))
      (node (ref "R22") (pin "2") (pinfunction "2_2") (pintype "passive"))
      (node (ref "R26") (pin "1") (pinfunction "1_1") (pintype "passive"))
      (node (ref "R29") (pin "1") (pinfunction "1_1") (pintype "passive"))
    )
    (net (code "62") (name "Net-(Q7-C)") (class "Default")
      (node (ref "Q7") (pin "2") (pinfunction "C_2") (pintype "passive"))
      (node (ref "R28") (pin "1") (pinfunction "1_1") (pintype "passive"))
    )
    (net (code "63") (name "Net-(Q8-B)") (class "Default")
      (node (ref "C17") (pin "1") (pinfunction "1_1") (pintype "passive"))
      (node (ref "C18") (pin "1") (pinfunction "1_1") (pintype "passive"))
      (node (ref "Q8") (pin "1") (pinfunction "B_1") (pintype "passive"))
      (node (ref "R37") (pin "2") (pinfunction "2_2") (pintype "passive"))
      (node (ref "R39") (pin "2") (pinfunction "2_2") (pintype "passive"))
    )
    (net (code "64") (name "Net-(Q8-C)") (class "Default")
      (node (ref "C20") (pin "1") (pinfunction "1_1") (pintype "passive"))
      (node (ref "Q8") (pin "2") (pinfunction "C_2") (pintype "passive"))
      (node (ref "R31") (pin "1") (pinfunction "1_1") (pintype "passive"))
      (node (ref "R34") (pin "1") (pinfunction "1_1") (pintype "passive"))
      (node (ref "R40") (pin "2") (pinfunction "2_2") (pintype "passive"))
    )
    (net (code "65") (name "Net-(Q9-B)") (class "Default")
      (node (ref "C20") (pin "2") (pinfunction "2_2") (pintype "passive"))
      (node (ref "C21") (pin "1") (pinfunction "1_1") (pintype "passive"))
      (node (ref "Q9") (pin "1") (pinfunction "B_1") (pintype "passive"))
      (node (ref "R38") (pin "2") (pinfunction "2_2") (pintype "passive"))
      (node (ref "R40") (pin "1") (pinfunction "1_1") (pintype "passive"))
    )
    (net (code "66") (name "Net-(Q9-C)") (class "Default")
      (node (ref "C17") (pin "2") (pinfunction "2_2") (pintype "passive"))
      (node (ref "D13") (pin "A") (pinfunction "A_A") (pintype "passive"))
      (node (ref "Q9") (pin "2") (pinfunction "C_2") (pintype "passive"))
      (node (ref "R35") (pin "1") (pinfunction "1_1") (pintype "passive"))
      (node (ref "R36") (pin "1") (pinfunction "1_1") (pintype "passive"))
      (node (ref "R39") (pin "1") (pinfunction "1_1") (pintype "passive"))
    )
    (net (code "67") (name "Net-(Q10-D)") (class "Default")
      (node (ref "C32") (pin "+") (pinfunction "+_+") (pintype "passive"))
      (node (ref "Q10") (pin "3") (pinfunction "D_3") (pintype "passive"))
      (node (ref "R50") (pin "2") (pinfunction "2_2") (pintype "passive"))
    )
    (net (code "68") (name "Net-(Q10-G)") (class "Default")
      (node (ref "D12") (pin "A") (pinfunction "A_A") (pintype "passive"))
      (node (ref "Q10") (pin "1") (pinfunction "G_1") (pintype "passive"))
    )
    (net (code "69") (name "Net-(Q10-S)") (class "Default")
      (node (ref "C7") (pin "2") (pinfunction "2_2") (pintype "passive"))
      (node (ref "Q10") (pin "2") (pinfunction "S_2") (pintype "passive"))
      (node (ref "Q5") (pin "2") (pinfunction "S_2") (pintype "passive"))
      (node (ref "R48") (pin "2") (pinfunction "2_2") (pintype "passive"))
    )
    (net (code "70") (name "Net-(R42-Pad1)") (class "Default")
      (node (ref "R42") (pin "1") (pinfunction "1_1") (pintype "passive"))
      (node (ref "VR4") (pin "3") (pinfunction "3_3") (pintype "passive"))
    )
    (net (code "71") (name "Net-(R53-Pad2)") (class "Default")
      (node (ref "R53") (pin "2") (pinfunction "2_2") (pintype "passive"))
      (node (ref "VR1") (pin "3") (pinfunction "3_3") (pintype "passive"))
    )
    (net (code "72") (name "Net-(SW1-S)") (class "Default")
      (node (ref "R55") (pin "1") (pinfunction "1_1") (pintype "passive"))
      (node (ref "SW1") (pin "2") (pinfunction "S_2") (pintype "passive"))
    )
    (net (code "73") (name "VB") (class "Default")
      (node (ref "C25") (pin "+") (pinfunction "+_+") (pintype "passive"))
      (node (ref "R11") (pin "1") (pinfunction "1_1") (pintype "passive"))
      (node (ref "R12") (pin "1") (pinfunction "1_1") (pintype "passive"))
      (node (ref "R14") (pin "1") (pinfunction "1_1") (pintype "passive"))
      (node (ref "R15") (pin "1") (pinfunction "1_1") (pintype "passive"))
      (node (ref "R24") (pin "1") (pinfunction "1_1") (pintype "passive"))
      (node (ref "R43") (pin "1") (pinfunction "1_1") (pintype "passive"))
      (node (ref "R44") (pin "1") (pinfunction "1_1") (pintype "passive"))
      (node (ref "R48") (pin "1") (pinfunction "1_1") (pintype "passive"))
      (node (ref "R5") (pin "2") (pinfunction "2_2") (pintype "passive"))
      (node (ref "R50") (pin "1") (pinfunction "1_1") (pintype "passive"))
      (node (ref "R51") (pin "1") (pinfunction "1_1") (pintype "passive"))
      (node (ref "R6") (pin "2") (pinfunction "2_2") (pintype "passive"))
      (node (ref "R8") (pin "1") (pinfunction "1_1") (pintype "passive"))
    )
  )
)
